# Ethernet_Module_r1.net
KiCad netlist of a schematic drawn in EAGLE
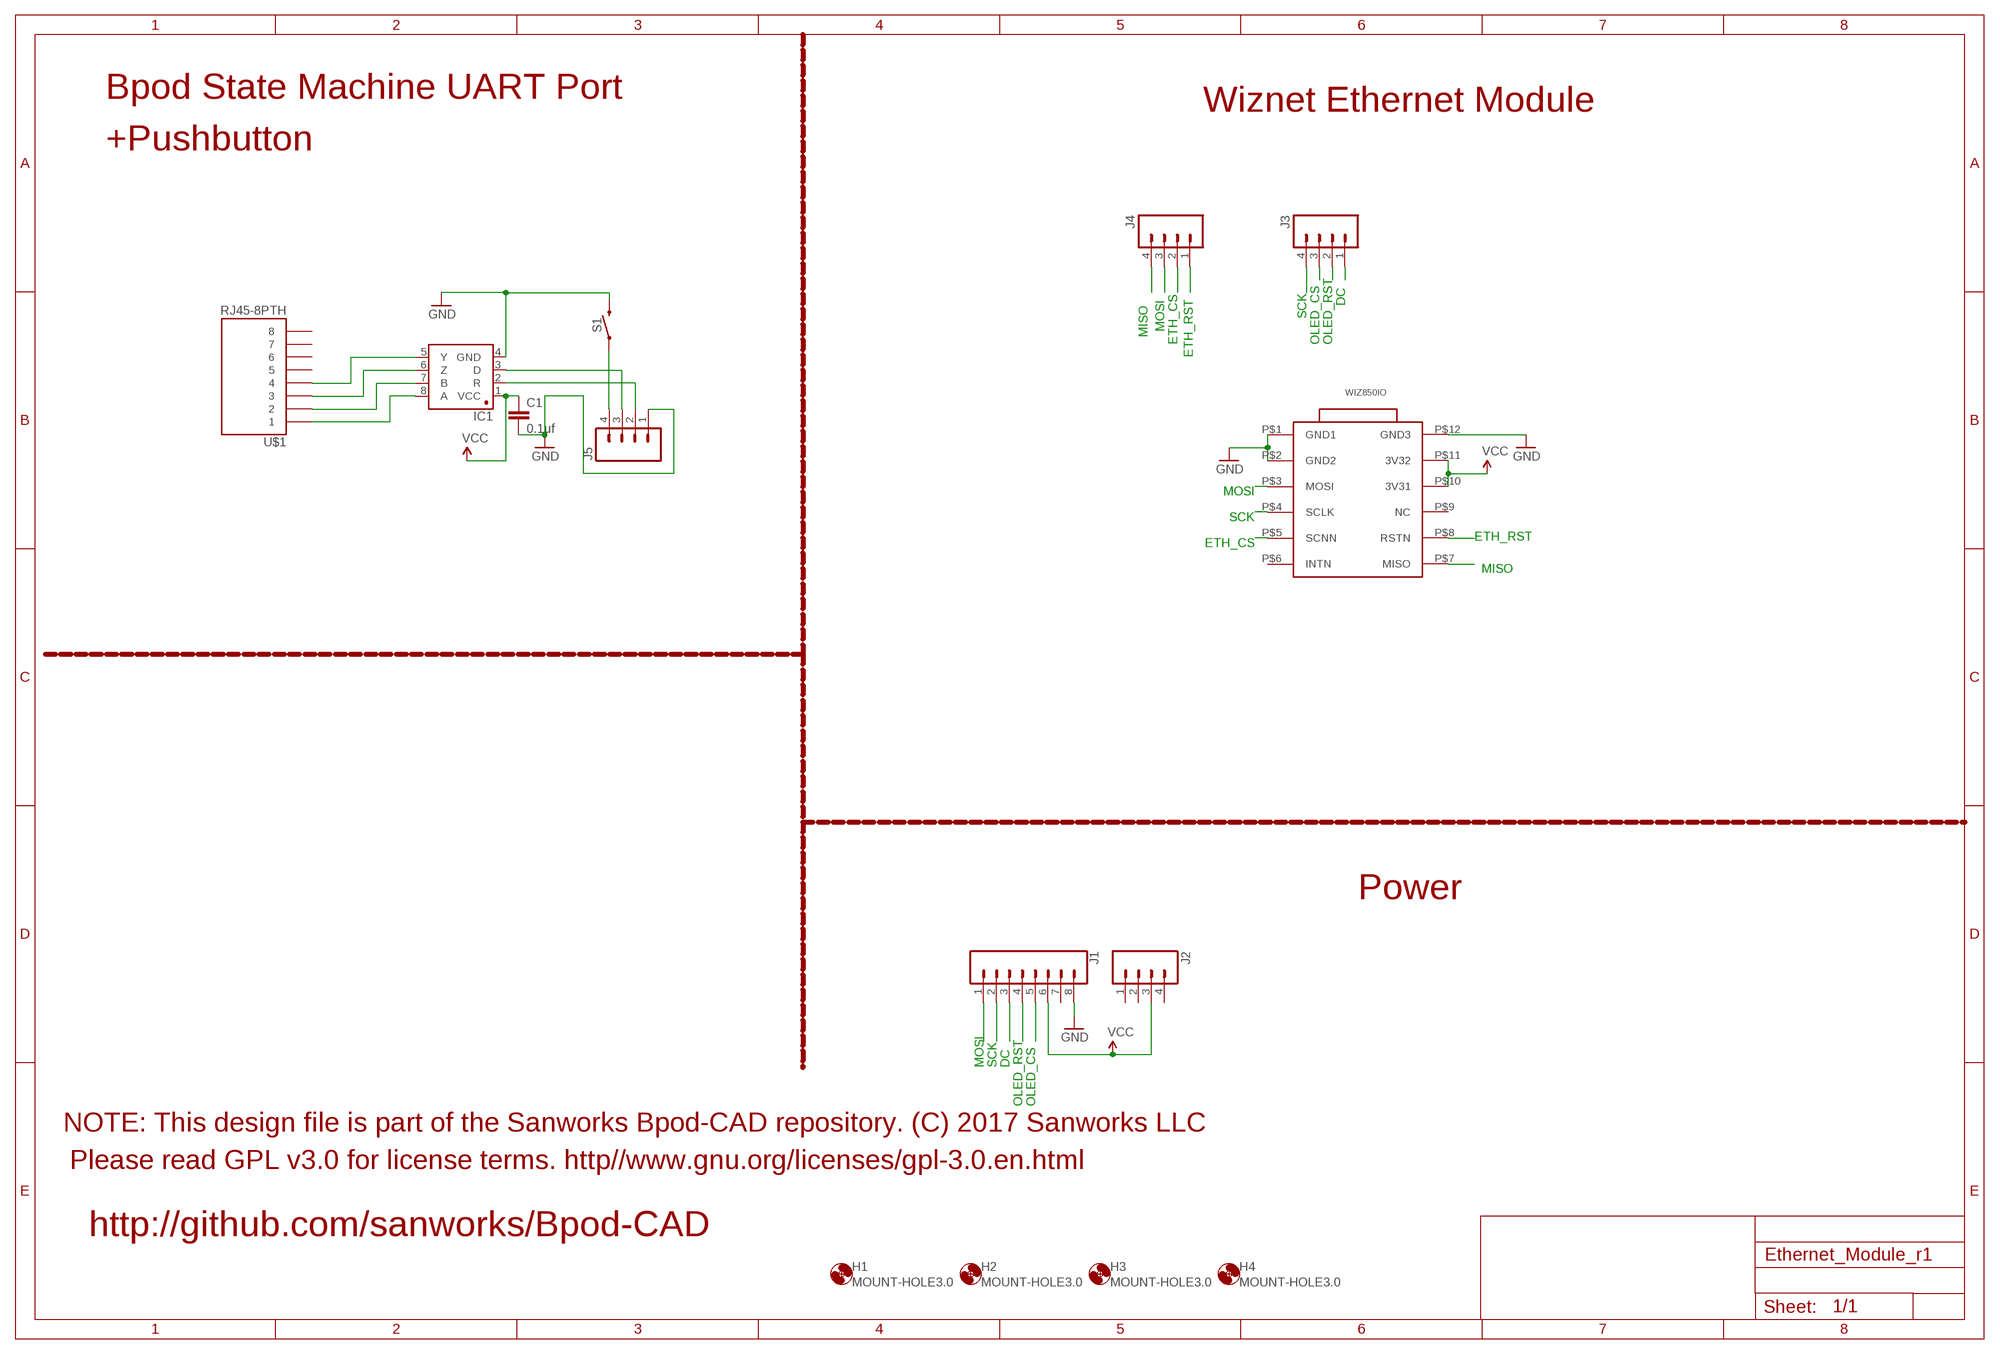
[diagram p0: schematic, sheet 1]

(export (version "E")
  (design (tool "Eeschema 10.0.6"))
  (components
    (comp (ref "C1")
      (value "0.1uf")
      (footprint "eagle-import:1206@1")
      (libsource (lib "eagle-import") (part "CAP1206"))
    )
    (comp (ref "H1")
      (value "MOUNT-HOLE3.0")
      (footprint "eagle-import:3,0")
      (libsource (lib "eagle-import") (part "MOUNT-HOLE3.0"))
    )
    (comp (ref "H2")
      (value "MOUNT-HOLE3.0")
      (footprint "eagle-import:3,0")
      (libsource (lib "eagle-import") (part "MOUNT-HOLE3.0"))
    )
    (comp (ref "H3")
      (value "MOUNT-HOLE3.0")
      (footprint "eagle-import:3,0")
      (libsource (lib "eagle-import") (part "MOUNT-HOLE3.0"))
    )
    (comp (ref "H4")
      (value "MOUNT-HOLE3.0")
      (footprint "eagle-import:3,0")
      (libsource (lib "eagle-import") (part "MOUNT-HOLE3.0"))
    )
    (comp (ref "IC1")
      (value "SN65HVD31DR")
      (footprint "eagle-import:SO08")
      (libsource (lib "eagle-import") (part "SN65HVD31DR"))
    )
    (comp (ref "J1")
      (value "CONN_08LONGPADS")
      (footprint "eagle-import:1X08_LONGPADS")
      (libsource (lib "eagle-import") (part "CONN_08LONGPADS"))
    )
    (comp (ref "J2")
      (value "M04PTH")
      (footprint "eagle-import:1X04")
      (libsource (lib "eagle-import") (part "M04PTH"))
    )
    (comp (ref "J3")
      (value "M04PTH")
      (footprint "eagle-import:1X04")
      (libsource (lib "eagle-import") (part "M04PTH"))
    )
    (comp (ref "J4")
      (value "M04PTH")
      (footprint "eagle-import:1X04")
      (libsource (lib "eagle-import") (part "M04PTH"))
    )
    (comp (ref "J5")
      (value "M04PTH")
      (footprint "eagle-import:1X04")
      (libsource (lib "eagle-import") (part "M04PTH"))
    )
    (comp (ref "S1")
      (value "MOMENTARY-SWITCH-SPST-SMD-5.2MM")
      (footprint "eagle-import:TACTILE_SWITCH_SMD_5.2MM")
      (libsource (lib "eagle-import") (part "MOMENTARY-SWITCH-SPST-SMD-5.2MM"))
    )
    (comp (ref "U$1")
      (value "RJ45-8PTH")
      (footprint "eagle-import:RJ45-8")
      (libsource (lib "eagle-import") (part "RJ45-8PTH"))
    )
    (comp (ref "WIZ850IO")
      (value "WIZ850IO")
      (footprint "eagle-import:WIZ850IO")
      (libsource (lib "eagle-import") (part "WIZ850IO"))
    )
  )
  (nets
    (net (code "1") (name "/DC") (class "Default")
      (node (ref "J1") (pin "3") (pinfunction "3_3") (pintype "passive"))
      (node (ref "J3") (pin "1") (pinfunction "1_1") (pintype "passive"))
    )
    (net (code "2") (name "/ETH_CS") (class "Default")
      (node (ref "J4") (pin "2") (pinfunction "2_2") (pintype "passive"))
      (node (ref "WIZ850IO") (pin "P$5") (pinfunction "SCNN_P$5") (pintype "bidirectional"))
    )
    (net (code "3") (name "/ETH_RST") (class "Default")
      (node (ref "J4") (pin "1") (pinfunction "1_1") (pintype "passive"))
      (node (ref "WIZ850IO") (pin "P$8") (pinfunction "RSTN_P$8") (pintype "bidirectional"))
    )
    (net (code "4") (name "/MISO") (class "Default")
      (node (ref "J4") (pin "4") (pinfunction "4_4") (pintype "passive"))
      (node (ref "WIZ850IO") (pin "P$7") (pinfunction "MISO_P$7") (pintype "bidirectional"))
    )
    (net (code "5") (name "/MOSI") (class "Default")
      (node (ref "J1") (pin "1") (pinfunction "1_1") (pintype "passive"))
      (node (ref "J4") (pin "3") (pinfunction "3_3") (pintype "passive"))
      (node (ref "WIZ850IO") (pin "P$3") (pinfunction "MOSI_P$3") (pintype "bidirectional"))
    )
    (net (code "6") (name "/OLED_CS") (class "Default")
      (node (ref "J1") (pin "5") (pinfunction "5_5") (pintype "passive"))
      (node (ref "J3") (pin "3") (pinfunction "3_3") (pintype "passive"))
    )
    (net (code "7") (name "/OLED_RST") (class "Default")
      (node (ref "J1") (pin "4") (pinfunction "4_4") (pintype "passive"))
      (node (ref "J3") (pin "2") (pinfunction "2_2") (pintype "passive"))
    )
    (net (code "8") (name "/SCK") (class "Default")
      (node (ref "J1") (pin "2") (pinfunction "2_2") (pintype "passive"))
      (node (ref "J3") (pin "4") (pinfunction "4_4") (pintype "passive"))
      (node (ref "WIZ850IO") (pin "P$4") (pinfunction "SCLK_P$4") (pintype "bidirectional"))
    )
    (net (code "9") (name "GND") (class "Default")
      (node (ref "C1") (pin "2") (pinfunction "2_2") (pintype "passive"))
      (node (ref "IC1") (pin "4") (pinfunction "GND_4") (pintype "bidirectional"))
      (node (ref "J1") (pin "8") (pinfunction "8_8") (pintype "passive"))
      (node (ref "J5") (pin "1") (pinfunction "1_1") (pintype "passive"))
      (node (ref "S1") (pin "3") (pinfunction "2_3") (pintype "passive"))
      (node (ref "WIZ850IO") (pin "P$1") (pinfunction "GND1_P$1") (pintype "bidirectional"))
      (node (ref "WIZ850IO") (pin "P$12") (pinfunction "GND3_P$12") (pintype "bidirectional"))
      (node (ref "WIZ850IO") (pin "P$2") (pinfunction "GND2_P$2") (pintype "bidirectional"))
    )
    (net (code "10") (name "Net-(IC1-A)") (class "Default")
      (node (ref "IC1") (pin "8") (pinfunction "A_8") (pintype "bidirectional"))
      (node (ref "U$1") (pin "1") (pinfunction "1_1") (pintype "bidirectional"))
    )
    (net (code "11") (name "Net-(IC1-B)") (class "Default")
      (node (ref "IC1") (pin "7") (pinfunction "B_7") (pintype "bidirectional"))
      (node (ref "U$1") (pin "2") (pinfunction "2_2") (pintype "bidirectional"))
    )
    (net (code "12") (name "Net-(IC1-D)") (class "Default")
      (node (ref "IC1") (pin "3") (pinfunction "D_3") (pintype "bidirectional"))
      (node (ref "J5") (pin "3") (pinfunction "3_3") (pintype "passive"))
    )
    (net (code "13") (name "Net-(IC1-R)") (class "Default")
      (node (ref "IC1") (pin "2") (pinfunction "R_2") (pintype "bidirectional"))
      (node (ref "J5") (pin "2") (pinfunction "2_2") (pintype "passive"))
    )
    (net (code "14") (name "Net-(IC1-Y)") (class "Default")
      (node (ref "IC1") (pin "5") (pinfunction "Y_5") (pintype "bidirectional"))
      (node (ref "U$1") (pin "4") (pinfunction "4_4") (pintype "bidirectional"))
    )
    (net (code "15") (name "Net-(IC1-Z)") (class "Default")
      (node (ref "IC1") (pin "6") (pinfunction "Z_6") (pintype "bidirectional"))
      (node (ref "U$1") (pin "3") (pinfunction "3_3") (pintype "bidirectional"))
    )
    (net (code "16") (name "Net-(J5-Pad4)") (class "Default")
      (node (ref "J5") (pin "4") (pinfunction "4_4") (pintype "passive"))
      (node (ref "S1") (pin "1") (pinfunction "1_1") (pintype "passive"))
    )
    (net (code "17") (name "VCC") (class "Default")
      (node (ref "C1") (pin "1") (pinfunction "1_1") (pintype "passive"))
      (node (ref "IC1") (pin "1") (pinfunction "VCC_1") (pintype "bidirectional"))
      (node (ref "J1") (pin "6") (pinfunction "6_6") (pintype "passive"))
      (node (ref "J2") (pin "3") (pinfunction "3_3") (pintype "passive"))
      (node (ref "WIZ850IO") (pin "P$10") (pinfunction "3V31_P$10") (pintype "bidirectional"))
      (node (ref "WIZ850IO") (pin "P$11") (pinfunction "3V32_P$11") (pintype "bidirectional"))
    )
    (net (code "18") (name "unconnected-(J1-Pad7)") (class "Default")
      (node (ref "J1") (pin "7") (pinfunction "7_7") (pintype "passive"))
    )
    (net (code "19") (name "unconnected-(J2-Pad1)") (class "Default")
      (node (ref "J2") (pin "1") (pinfunction "1_1") (pintype "passive"))
    )
    (net (code "20") (name "unconnected-(J2-Pad2)") (class "Default")
      (node (ref "J2") (pin "2") (pinfunction "2_2") (pintype "passive"))
    )
    (net (code "21") (name "unconnected-(J2-Pad4)") (class "Default")
      (node (ref "J2") (pin "4") (pinfunction "4_4") (pintype "passive"))
    )
    (net (code "22") (name "unconnected-(U$1-Pad5)") (class "Default")
      (node (ref "U$1") (pin "5") (pinfunction "5_5") (pintype "bidirectional"))
    )
    (net (code "23") (name "unconnected-(U$1-Pad6)") (class "Default")
      (node (ref "U$1") (pin "6") (pinfunction "6_6") (pintype "bidirectional"))
    )
    (net (code "24") (name "unconnected-(U$1-Pad7)") (class "Default")
      (node (ref "U$1") (pin "7") (pinfunction "7_7") (pintype "bidirectional"))
    )
    (net (code "25") (name "unconnected-(U$1-Pad8)") (class "Default")
      (node (ref "U$1") (pin "8") (pinfunction "8_8") (pintype "bidirectional"))
    )
    (net (code "26") (name "unconnected-(WIZ850IO-INTN-PadP$6)") (class "Default")
      (node (ref "WIZ850IO") (pin "P$6") (pinfunction "INTN_P$6") (pintype "bidirectional"))
    )
    (net (code "27") (name "unconnected-(WIZ850IO-NC-PadP$9)") (class "Default")
      (node (ref "WIZ850IO") (pin "P$9") (pinfunction "NC_P$9") (pintype "bidirectional"))
    )
  )
)
